# Macro_Keyboard_32u4_RC_SK6812_LED_Ver2_1.net
KiCad netlist of a schematic drawn in EAGLE
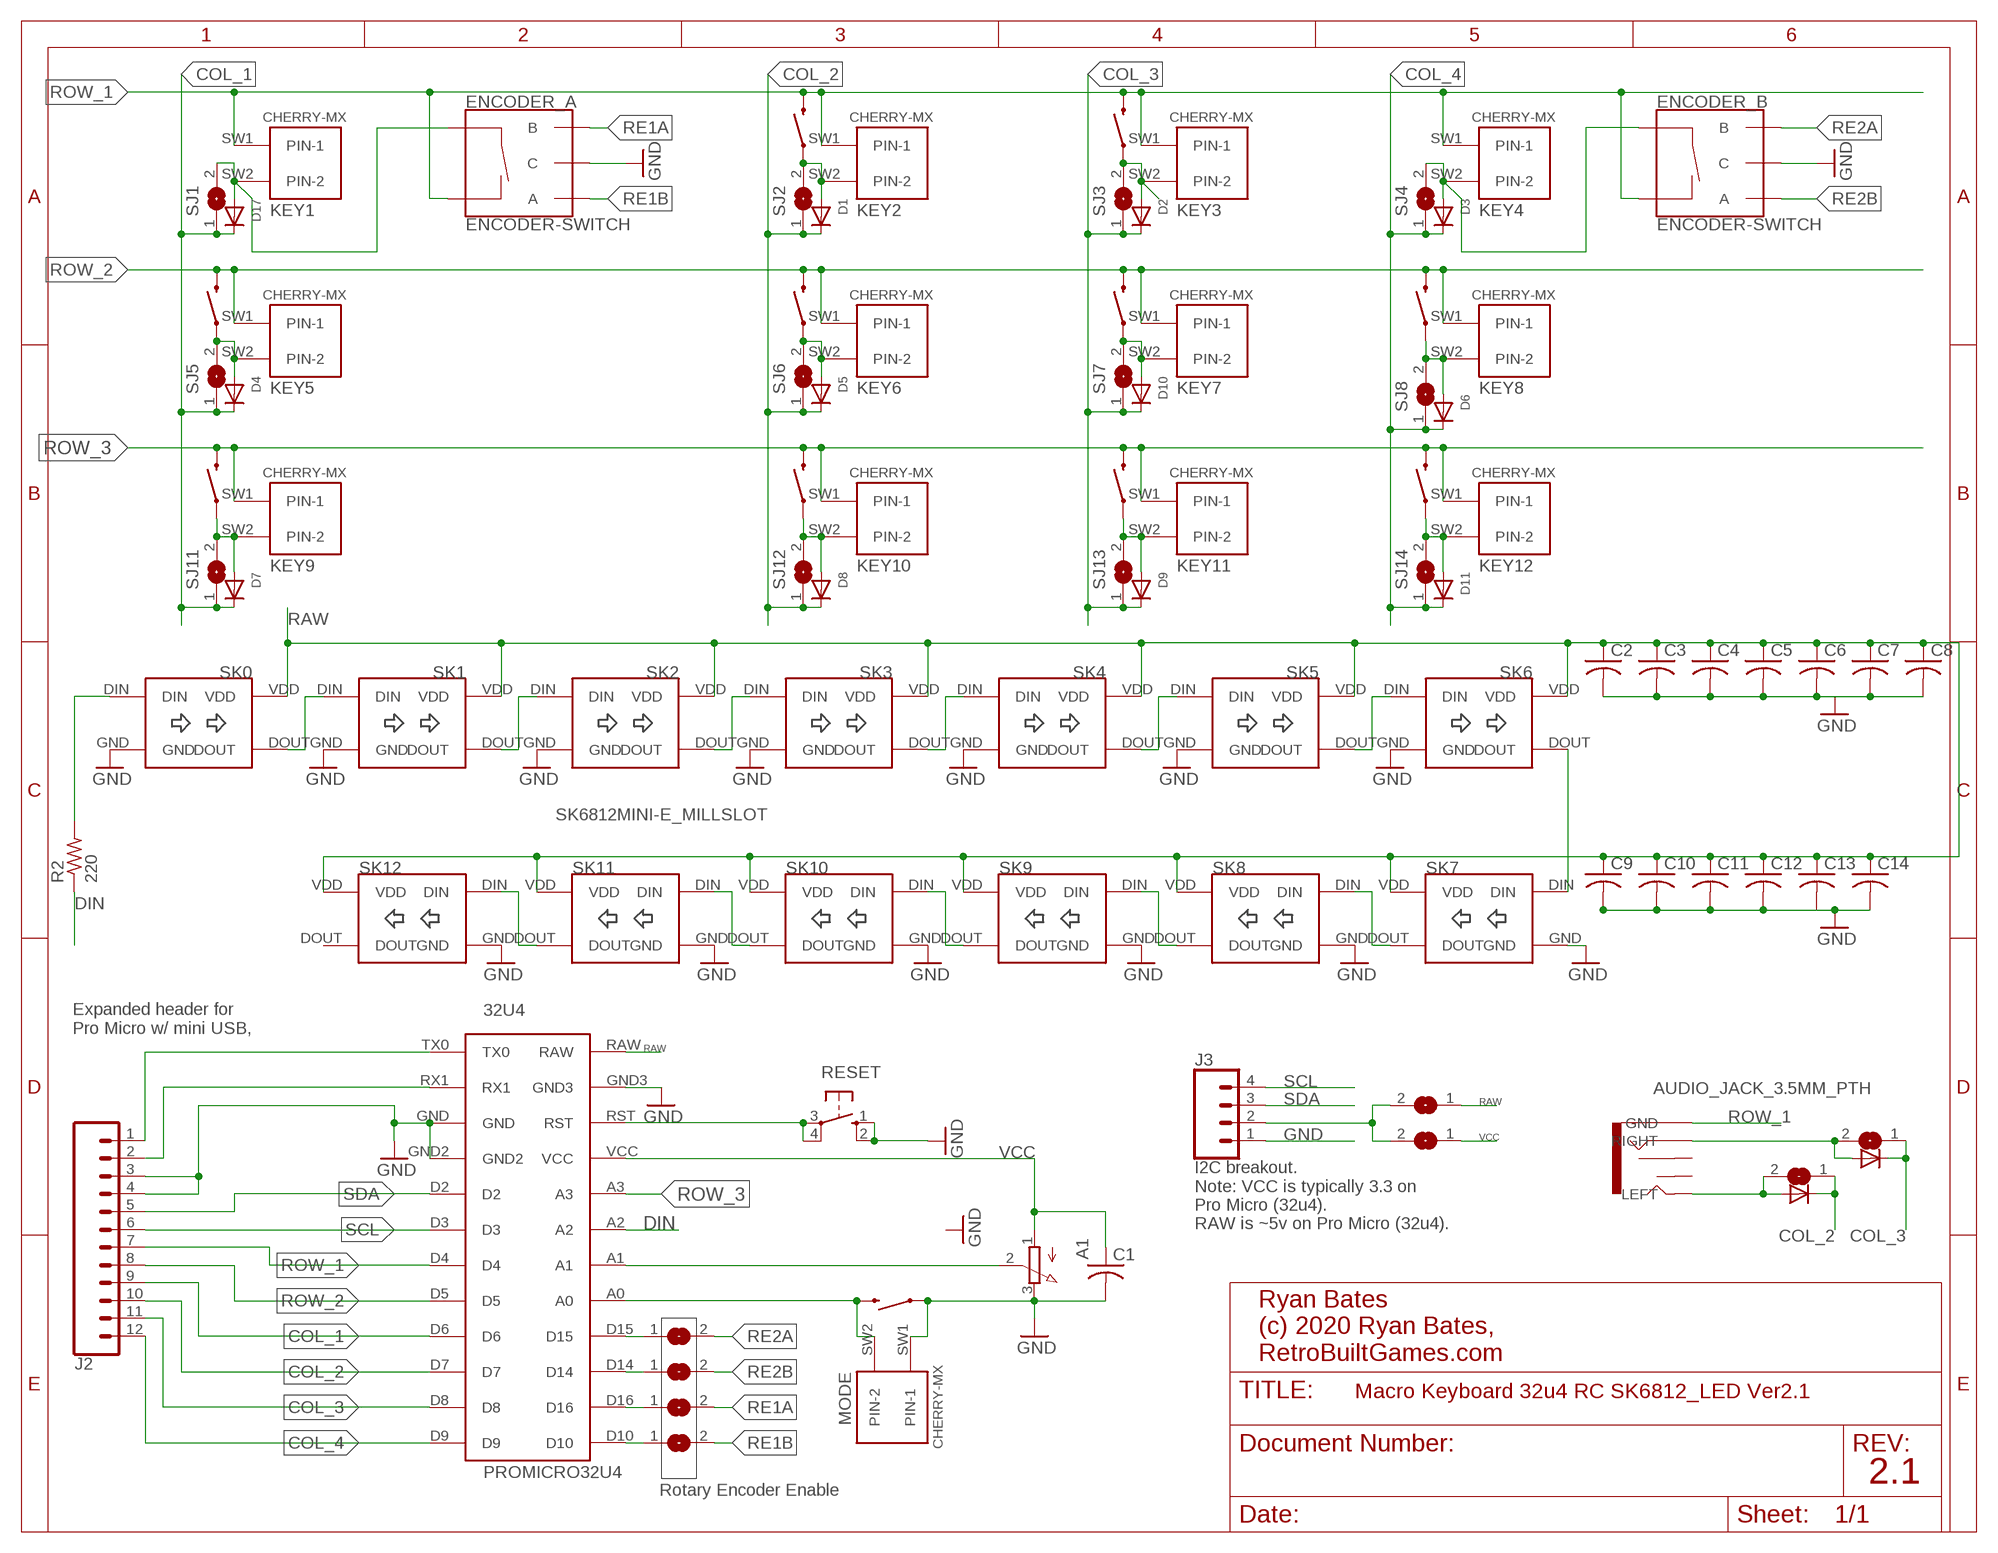
[diagram p0: schematic, sheet 1]

(export (version "E")
  (design (tool "Eeschema 10.0.6"))
  (components
    (comp (ref "32U4")
      (value "PROMICRO32U4")
      (footprint "eagle-import:PROMICRO32U4")
      (libsource (lib "eagle-import") (part "PROMICRO32U4"))
    )
    (comp (ref "A1")
      (value "3RP/1610N")
      (footprint "eagle-import:3RP_1610N")
      (libsource (lib "eagle-import") (part "3RP/1610N"))
    )
    (comp (ref "C1")
      (value "C-USC1206")
      (footprint "eagle-import:C1206")
      (libsource (lib "eagle-import") (part "C-USC1206"))
    )
    (comp (ref "C2")
      (value "C-USC0805K")
      (footprint "eagle-import:C0805K")
      (libsource (lib "eagle-import") (part "C-USC0805K"))
    )
    (comp (ref "C3")
      (value "C-USC0805K")
      (footprint "eagle-import:C0805K")
      (libsource (lib "eagle-import") (part "C-USC0805K"))
    )
    (comp (ref "C4")
      (value "C-USC0805K")
      (footprint "eagle-import:C0805K")
      (libsource (lib "eagle-import") (part "C-USC0805K"))
    )
    (comp (ref "C5")
      (value "C-USC0805K")
      (footprint "eagle-import:C0805K")
      (libsource (lib "eagle-import") (part "C-USC0805K"))
    )
    (comp (ref "C6")
      (value "C-USC0805K")
      (footprint "eagle-import:C0805K")
      (libsource (lib "eagle-import") (part "C-USC0805K"))
    )
    (comp (ref "C7")
      (value "C-USC0805K")
      (footprint "eagle-import:C0805K")
      (libsource (lib "eagle-import") (part "C-USC0805K"))
    )
    (comp (ref "C8")
      (value "C-USC0805K")
      (footprint "eagle-import:C0805K")
      (libsource (lib "eagle-import") (part "C-USC0805K"))
    )
    (comp (ref "C9")
      (value "C-USC0805K")
      (footprint "eagle-import:C0805K")
      (libsource (lib "eagle-import") (part "C-USC0805K"))
    )
    (comp (ref "C10")
      (value "C-USC0805K")
      (footprint "eagle-import:C0805K")
      (libsource (lib "eagle-import") (part "C-USC0805K"))
    )
    (comp (ref "C11")
      (value "C-USC0805K")
      (footprint "eagle-import:C0805K")
      (libsource (lib "eagle-import") (part "C-USC0805K"))
    )
    (comp (ref "C12")
      (value "C-USC0805K")
      (footprint "eagle-import:C0805K")
      (libsource (lib "eagle-import") (part "C-USC0805K"))
    )
    (comp (ref "C13")
      (value "C-USC0805K")
      (footprint "eagle-import:C0805K")
      (libsource (lib "eagle-import") (part "C-USC0805K"))
    )
    (comp (ref "C14")
      (value "C-USC0805K")
      (footprint "eagle-import:C0805K")
      (libsource (lib "eagle-import") (part "C-USC0805K"))
    )
    (comp (ref "D1")
      (value "DIODESOD-123")
      (footprint "eagle-import:SOD-123")
      (libsource (lib "eagle-import") (part "DIODESOD-123"))
    )
    (comp (ref "D2")
      (value "DIODESOD-123")
      (footprint "eagle-import:SOD-123")
      (libsource (lib "eagle-import") (part "DIODESOD-123"))
    )
    (comp (ref "D3")
      (value "DIODESOD-123")
      (footprint "eagle-import:SOD-123")
      (libsource (lib "eagle-import") (part "DIODESOD-123"))
    )
    (comp (ref "D4")
      (value "DIODESOD-123")
      (footprint "eagle-import:SOD-123")
      (libsource (lib "eagle-import") (part "DIODESOD-123"))
    )
    (comp (ref "D5")
      (value "DIODESOD-123")
      (footprint "eagle-import:SOD-123")
      (libsource (lib "eagle-import") (part "DIODESOD-123"))
    )
    (comp (ref "D6")
      (value "DIODESOD-123")
      (footprint "eagle-import:SOD-123")
      (libsource (lib "eagle-import") (part "DIODESOD-123"))
    )
    (comp (ref "D7")
      (value "DIODESOD-123")
      (footprint "eagle-import:SOD-123")
      (libsource (lib "eagle-import") (part "DIODESOD-123"))
    )
    (comp (ref "D8")
      (value "DIODESOD-123")
      (footprint "eagle-import:SOD-123")
      (libsource (lib "eagle-import") (part "DIODESOD-123"))
    )
    (comp (ref "D9")
      (value "DIODESOD-123")
      (footprint "eagle-import:SOD-123")
      (libsource (lib "eagle-import") (part "DIODESOD-123"))
    )
    (comp (ref "D10")
      (value "DIODESOD-123")
      (footprint "eagle-import:SOD-123")
      (libsource (lib "eagle-import") (part "DIODESOD-123"))
    )
    (comp (ref "D11")
      (value "DIODESOD-123")
      (footprint "eagle-import:SOD-123")
      (libsource (lib "eagle-import") (part "DIODESOD-123"))
    )
    (comp (ref "D15")
      (value "DIODESOD-123")
      (footprint "eagle-import:SOD-123")
      (libsource (lib "eagle-import") (part "DIODESOD-123"))
    )
    (comp (ref "D16")
      (value "DIODESOD-123")
      (footprint "eagle-import:SOD-123")
      (libsource (lib "eagle-import") (part "DIODESOD-123"))
    )
    (comp (ref "D17")
      (value "DIODESOD-123")
      (footprint "eagle-import:SOD-123")
      (libsource (lib "eagle-import") (part "DIODESOD-123"))
    )
    (comp (ref "ENCODER_A")
      (value "ENCODER-SWITCH")
      (footprint "eagle-import:ROTARY_ENC_PLAIN")
      (libsource (lib "eagle-import") (part "ENCODER-SWITCH"))
    )
    (comp (ref "ENCODER_B")
      (value "ENCODER-SWITCH")
      (footprint "eagle-import:ROTARY_ENC_PLAIN")
      (libsource (lib "eagle-import") (part "ENCODER-SWITCH"))
    )
    (comp (ref "J1")
      (value "AUDIO_JACK_3.5MM_PTH")
      (footprint "eagle-import:AUDIO-JACK")
      (libsource (lib "eagle-import") (part "AUDIO_JACK_3.5MM_PTH"))
    )
    (comp (ref "J2")
      (value "CONN_12NO_SILK")
      (footprint "eagle-import:1X12_NO_SILK")
      (libsource (lib "eagle-import") (part "CONN_12NO_SILK"))
    )
    (comp (ref "J3")
      (value "CONN_041X04_NO_SILK")
      (footprint "eagle-import:1X04_NO_SILK")
      (libsource (lib "eagle-import") (part "CONN_041X04_NO_SILK"))
    )
    (comp (ref "KEY1")
      (value "CHERRY-MX")
      (footprint "eagle-import:CHERRY-MX")
      (libsource (lib "eagle-import") (part "CHERRY-MX"))
    )
    (comp (ref "KEY2")
      (value "CHERRY-MX")
      (footprint "eagle-import:CHERRY-MX")
      (libsource (lib "eagle-import") (part "CHERRY-MX"))
    )
    (comp (ref "KEY3")
      (value "CHERRY-MX")
      (footprint "eagle-import:CHERRY-MX")
      (libsource (lib "eagle-import") (part "CHERRY-MX"))
    )
    (comp (ref "KEY4")
      (value "CHERRY-MX")
      (footprint "eagle-import:CHERRY-MX")
      (libsource (lib "eagle-import") (part "CHERRY-MX"))
    )
    (comp (ref "KEY5")
      (value "CHERRY-MX")
      (footprint "eagle-import:CHERRY-MX")
      (libsource (lib "eagle-import") (part "CHERRY-MX"))
    )
    (comp (ref "KEY6")
      (value "CHERRY-MX")
      (footprint "eagle-import:CHERRY-MX")
      (libsource (lib "eagle-import") (part "CHERRY-MX"))
    )
    (comp (ref "KEY7")
      (value "CHERRY-MX")
      (footprint "eagle-import:CHERRY-MX")
      (libsource (lib "eagle-import") (part "CHERRY-MX"))
    )
    (comp (ref "KEY8")
      (value "CHERRY-MX")
      (footprint "eagle-import:CHERRY-MX")
      (libsource (lib "eagle-import") (part "CHERRY-MX"))
    )
    (comp (ref "KEY9")
      (value "CHERRY-MX")
      (footprint "eagle-import:CHERRY-MX")
      (libsource (lib "eagle-import") (part "CHERRY-MX"))
    )
    (comp (ref "KEY10")
      (value "CHERRY-MX")
      (footprint "eagle-import:CHERRY-MX")
      (libsource (lib "eagle-import") (part "CHERRY-MX"))
    )
    (comp (ref "KEY11")
      (value "CHERRY-MX")
      (footprint "eagle-import:CHERRY-MX")
      (libsource (lib "eagle-import") (part "CHERRY-MX"))
    )
    (comp (ref "KEY12")
      (value "CHERRY-MX")
      (footprint "eagle-import:CHERRY-MX")
      (libsource (lib "eagle-import") (part "CHERRY-MX"))
    )
    (comp (ref "MODE")
      (value "CHERRY-MX")
      (footprint "eagle-import:CHERRY-MX")
      (libsource (lib "eagle-import") (part "CHERRY-MX"))
    )
    (comp (ref "R2")
      (value "220")
      (footprint "eagle-import:M1206")
      (libsource (lib "eagle-import") (part "R-US_M1206"))
    )
    (comp (ref "RESET")
      (value "10-XX")
      (footprint "eagle-import:B3F-10XX")
      (fields (field (name "MPN") "B3F-1000"))
      (libsource (lib "eagle-import") (part "10-XX"))
    )
    (comp (ref "S1")
      (value "MOMENTARY-SWITCH-SPST-PTH-12MM")
      (footprint "eagle-import:TACTILE_SWITCH_PTH_12MM")
      (libsource (lib "eagle-import") (part "MOMENTARY-SWITCH-SPST-PTH-12MM"))
    )
    (comp (ref "S2")
      (value "MOMENTARY-SWITCH-SPST-PTH-12MM")
      (footprint "eagle-import:TACTILE_SWITCH_PTH_12MM")
      (libsource (lib "eagle-import") (part "MOMENTARY-SWITCH-SPST-PTH-12MM"))
    )
    (comp (ref "S3")
      (value "MOMENTARY-SWITCH-SPST-PTH-12MM")
      (footprint "eagle-import:TACTILE_SWITCH_PTH_12MM")
      (libsource (lib "eagle-import") (part "MOMENTARY-SWITCH-SPST-PTH-12MM"))
    )
    (comp (ref "S4")
      (value "MOMENTARY-SWITCH-SPST-PTH-12MM")
      (footprint "eagle-import:TACTILE_SWITCH_PTH_12MM")
      (libsource (lib "eagle-import") (part "MOMENTARY-SWITCH-SPST-PTH-12MM"))
    )
    (comp (ref "S5")
      (value "MOMENTARY-SWITCH-SPST-PTH-12MM")
      (footprint "eagle-import:TACTILE_SWITCH_PTH_12MM")
      (libsource (lib "eagle-import") (part "MOMENTARY-SWITCH-SPST-PTH-12MM"))
    )
    (comp (ref "S6")
      (value "MOMENTARY-SWITCH-SPST-PTH-12MM")
      (footprint "eagle-import:TACTILE_SWITCH_PTH_12MM")
      (libsource (lib "eagle-import") (part "MOMENTARY-SWITCH-SPST-PTH-12MM"))
    )
    (comp (ref "S7")
      (value "MOMENTARY-SWITCH-SPST-PTH-12MM")
      (footprint "eagle-import:TACTILE_SWITCH_PTH_12MM")
      (libsource (lib "eagle-import") (part "MOMENTARY-SWITCH-SPST-PTH-12MM"))
    )
    (comp (ref "S8")
      (value "MOMENTARY-SWITCH-SPST-PTH-12MM")
      (footprint "eagle-import:TACTILE_SWITCH_PTH_12MM")
      (libsource (lib "eagle-import") (part "MOMENTARY-SWITCH-SPST-PTH-12MM"))
    )
    (comp (ref "S9")
      (value "MOMENTARY-SWITCH-SPST-PTH-12MM")
      (footprint "eagle-import:TACTILE_SWITCH_PTH_12MM")
      (libsource (lib "eagle-import") (part "MOMENTARY-SWITCH-SPST-PTH-12MM"))
    )
    (comp (ref "S10")
      (value "MOMENTARY-SWITCH-SPST-PTH-12MM")
      (footprint "eagle-import:TACTILE_SWITCH_PTH_12MM")
      (libsource (lib "eagle-import") (part "MOMENTARY-SWITCH-SPST-PTH-12MM"))
    )
    (comp (ref "S11")
      (value "MOMENTARY-SWITCH-SPST-PTH-12MM")
      (footprint "eagle-import:TACTILE_SWITCH_PTH_12MM")
      (libsource (lib "eagle-import") (part "MOMENTARY-SWITCH-SPST-PTH-12MM"))
    )
    (comp (ref "SJ1") (value "SJ") (footprint "eagle-import:SJ") (libsource (lib "eagle-import") (part "SJ")))
    (comp (ref "SJ2") (value "SJ") (footprint "eagle-import:SJ") (libsource (lib "eagle-import") (part "SJ")))
    (comp (ref "SJ3") (value "SJ") (footprint "eagle-import:SJ") (libsource (lib "eagle-import") (part "SJ")))
    (comp (ref "SJ4") (value "SJ") (footprint "eagle-import:SJ") (libsource (lib "eagle-import") (part "SJ")))
    (comp (ref "SJ5") (value "SJ") (footprint "eagle-import:SJ") (libsource (lib "eagle-import") (part "SJ")))
    (comp (ref "SJ6") (value "SJ") (footprint "eagle-import:SJ") (libsource (lib "eagle-import") (part "SJ")))
    (comp (ref "SJ7") (value "SJ") (footprint "eagle-import:SJ") (libsource (lib "eagle-import") (part "SJ")))
    (comp (ref "SJ8") (value "SJ") (footprint "eagle-import:SJ") (libsource (lib "eagle-import") (part "SJ")))
    (comp (ref "SJ9") (value "SJ") (footprint "eagle-import:SJ") (libsource (lib "eagle-import") (part "SJ")))
    (comp (ref "SJ10")
      (value "SJ")
      (footprint "eagle-import:SJ")
      (libsource (lib "eagle-import") (part "SJ"))
    )
    (comp (ref "SJ11")
      (value "SJ")
      (footprint "eagle-import:SJ")
      (libsource (lib "eagle-import") (part "SJ"))
    )
    (comp (ref "SJ12")
      (value "SJ")
      (footprint "eagle-import:SJ")
      (libsource (lib "eagle-import") (part "SJ"))
    )
    (comp (ref "SJ13")
      (value "SJ")
      (footprint "eagle-import:SJ")
      (libsource (lib "eagle-import") (part "SJ"))
    )
    (comp (ref "SJ14")
      (value "SJ")
      (footprint "eagle-import:SJ")
      (libsource (lib "eagle-import") (part "SJ"))
    )
    (comp (ref "SJ16")
      (value "SJ")
      (footprint "eagle-import:SJ")
      (libsource (lib "eagle-import") (part "SJ"))
    )
    (comp (ref "SJ17")
      (value "SJ")
      (footprint "eagle-import:SJ")
      (libsource (lib "eagle-import") (part "SJ"))
    )
    (comp (ref "SJ18")
      (value "SJ")
      (footprint "eagle-import:SJ")
      (libsource (lib "eagle-import") (part "SJ"))
    )
    (comp (ref "SJ19")
      (value "SJ")
      (footprint "eagle-import:SJ")
      (libsource (lib "eagle-import") (part "SJ"))
    )
    (comp (ref "SJ20")
      (value "SJ")
      (footprint "eagle-import:SJ")
      (libsource (lib "eagle-import") (part "SJ"))
    )
    (comp (ref "SJ21")
      (value "SJ")
      (footprint "eagle-import:SJ")
      (libsource (lib "eagle-import") (part "SJ"))
    )
    (comp (ref "SK0")
      (value "SK6812MINI-E_MILLSLOT")
      (footprint "eagle-import:SK6812MINI-E_MILLSLOT")
      (libsource (lib "eagle-import") (part "SK6812MINI-E_MILLSLOT"))
    )
    (comp (ref "SK1")
      (value "SK6812MINI-E_MILLSLOT")
      (footprint "eagle-import:SK6812MINI-E_MILLSLOT")
      (libsource (lib "eagle-import") (part "SK6812MINI-E_MILLSLOT"))
    )
    (comp (ref "SK2")
      (value "SK6812MINI-E_MILLSLOT")
      (footprint "eagle-import:SK6812MINI-E_MILLSLOT")
      (libsource (lib "eagle-import") (part "SK6812MINI-E_MILLSLOT"))
    )
    (comp (ref "SK3")
      (value "SK6812MINI-E_MILLSLOT")
      (footprint "eagle-import:SK6812MINI-E_MILLSLOT")
      (libsource (lib "eagle-import") (part "SK6812MINI-E_MILLSLOT"))
    )
    (comp (ref "SK4")
      (value "SK6812MINI-E_MILLSLOT")
      (footprint "eagle-import:SK6812MINI-E_MILLSLOT")
      (libsource (lib "eagle-import") (part "SK6812MINI-E_MILLSLOT"))
    )
    (comp (ref "SK5")
      (value "SK6812MINI-E_MILLSLOT")
      (footprint "eagle-import:SK6812MINI-E_MILLSLOT")
      (libsource (lib "eagle-import") (part "SK6812MINI-E_MILLSLOT"))
    )
    (comp (ref "SK6")
      (value "SK6812MINI-E_MILLSLOT")
      (footprint "eagle-import:SK6812MINI-E_MILLSLOT")
      (libsource (lib "eagle-import") (part "SK6812MINI-E_MILLSLOT"))
    )
    (comp (ref "SK7")
      (value "SK6812MINI-E_MILLSLOT")
      (footprint "eagle-import:SK6812MINI-E_MILLSLOT")
      (libsource (lib "eagle-import") (part "SK6812MINI-E_MILLSLOT"))
    )
    (comp (ref "SK8")
      (value "SK6812MINI-E_MILLSLOT")
      (footprint "eagle-import:SK6812MINI-E_MILLSLOT")
      (libsource (lib "eagle-import") (part "SK6812MINI-E_MILLSLOT"))
    )
    (comp (ref "SK9")
      (value "SK6812MINI-E_MILLSLOT")
      (footprint "eagle-import:SK6812MINI-E_MILLSLOT")
      (libsource (lib "eagle-import") (part "SK6812MINI-E_MILLSLOT"))
    )
    (comp (ref "SK10")
      (value "SK6812MINI-E_MILLSLOT")
      (footprint "eagle-import:SK6812MINI-E_MILLSLOT")
      (libsource (lib "eagle-import") (part "SK6812MINI-E_MILLSLOT"))
    )
    (comp (ref "SK11")
      (value "SK6812MINI-E_MILLSLOT")
      (footprint "eagle-import:SK6812MINI-E_MILLSLOT")
      (libsource (lib "eagle-import") (part "SK6812MINI-E_MILLSLOT"))
    )
    (comp (ref "SK12")
      (value "SK6812MINI-E_MILLSLOT")
      (footprint "eagle-import:SK6812MINI-E_MILLSLOT")
      (libsource (lib "eagle-import") (part "SK6812MINI-E_MILLSLOT"))
    )
  )
  (nets
    (net (code "1") (name "/DIN") (class "Default")
      (node (ref "32U4") (pin "A2") (pinfunction "A2_A2") (pintype "bidirectional"))
      (node (ref "R2") (pin "1") (pinfunction "1_1") (pintype "passive"))
    )
    (net (code "2") (name "/RAW") (class "Default")
      (node (ref "32U4") (pin "RAW") (pinfunction "RAW_RAW") (pintype "bidirectional"))
      (node (ref "C10") (pin "1") (pinfunction "1_1") (pintype "passive"))
      (node (ref "C11") (pin "1") (pinfunction "1_1") (pintype "passive"))
      (node (ref "C12") (pin "1") (pinfunction "1_1") (pintype "passive"))
      (node (ref "C13") (pin "1") (pinfunction "1_1") (pintype "passive"))
      (node (ref "C14") (pin "1") (pinfunction "1_1") (pintype "passive"))
      (node (ref "C2") (pin "1") (pinfunction "1_1") (pintype "passive"))
      (node (ref "C3") (pin "1") (pinfunction "1_1") (pintype "passive"))
      (node (ref "C4") (pin "1") (pinfunction "1_1") (pintype "passive"))
      (node (ref "C5") (pin "1") (pinfunction "1_1") (pintype "passive"))
      (node (ref "C6") (pin "1") (pinfunction "1_1") (pintype "passive"))
      (node (ref "C7") (pin "1") (pinfunction "1_1") (pintype "passive"))
      (node (ref "C8") (pin "1") (pinfunction "1_1") (pintype "passive"))
      (node (ref "C9") (pin "1") (pinfunction "1_1") (pintype "passive"))
      (node (ref "SJ9") (pin "1") (pinfunction "1_1") (pintype "passive"))
      (node (ref "SK0") (pin "VDD") (pinfunction "VDD_VDD") (pintype "bidirectional"))
      (node (ref "SK1") (pin "VDD") (pinfunction "VDD_VDD") (pintype "bidirectional"))
      (node (ref "SK10") (pin "VDD") (pinfunction "VDD_VDD") (pintype "bidirectional"))
      (node (ref "SK11") (pin "VDD") (pinfunction "VDD_VDD") (pintype "bidirectional"))
      (node (ref "SK12") (pin "VDD") (pinfunction "VDD_VDD") (pintype "bidirectional"))
      (node (ref "SK2") (pin "VDD") (pinfunction "VDD_VDD") (pintype "bidirectional"))
      (node (ref "SK3") (pin "VDD") (pinfunction "VDD_VDD") (pintype "bidirectional"))
      (node (ref "SK4") (pin "VDD") (pinfunction "VDD_VDD") (pintype "bidirectional"))
      (node (ref "SK5") (pin "VDD") (pinfunction "VDD_VDD") (pintype "bidirectional"))
      (node (ref "SK6") (pin "VDD") (pinfunction "VDD_VDD") (pintype "bidirectional"))
      (node (ref "SK7") (pin "VDD") (pinfunction "VDD_VDD") (pintype "bidirectional"))
      (node (ref "SK8") (pin "VDD") (pinfunction "VDD_VDD") (pintype "bidirectional"))
      (node (ref "SK9") (pin "VDD") (pinfunction "VDD_VDD") (pintype "bidirectional"))
    )
    (net (code "3") (name "/VCC") (class "Default")
      (node (ref "32U4") (pin "VCC") (pinfunction "VCC_VCC") (pintype "bidirectional"))
      (node (ref "A1") (pin "1") (pinfunction "A_1") (pintype "passive"))
      (node (ref "C1") (pin "1") (pinfunction "1_1") (pintype "passive"))
      (node (ref "SJ10") (pin "1") (pinfunction "1_1") (pintype "passive"))
    )
    (net (code "4") (name "COL_1") (class "Default")
      (node (ref "32U4") (pin "D6") (pinfunction "D6_D6") (pintype "bidirectional"))
      (node (ref "D17") (pin "C") (pinfunction "C_C") (pintype "passive"))
      (node (ref "D4") (pin "C") (pinfunction "C_C") (pintype "passive"))
      (node (ref "D7") (pin "C") (pinfunction "C_C") (pintype "passive"))
      (node (ref "J2") (pin "9") (pinfunction "9_9") (pintype "passive"))
      (node (ref "SJ1") (pin "1") (pinfunction "1_1") (pintype "passive"))
      (node (ref "SJ11") (pin "1") (pinfunction "1_1") (pintype "passive"))
      (node (ref "SJ5") (pin "1") (pinfunction "1_1") (pintype "passive"))
    )
    (net (code "5") (name "COL_2") (class "Default")
      (node (ref "32U4") (pin "D7") (pinfunction "D7_D7") (pintype "bidirectional"))
      (node (ref "D1") (pin "C") (pinfunction "C_C") (pintype "passive"))
      (node (ref "D15") (pin "C") (pinfunction "C_C") (pintype "passive"))
      (node (ref "D5") (pin "C") (pinfunction "C_C") (pintype "passive"))
      (node (ref "D8") (pin "C") (pinfunction "C_C") (pintype "passive"))
      (node (ref "J2") (pin "10") (pinfunction "10_10") (pintype "passive"))
      (node (ref "SJ12") (pin "1") (pinfunction "1_1") (pintype "passive"))
      (node (ref "SJ16") (pin "1") (pinfunction "1_1") (pintype "passive"))
      (node (ref "SJ2") (pin "1") (pinfunction "1_1") (pintype "passive"))
      (node (ref "SJ6") (pin "1") (pinfunction "1_1") (pintype "passive"))
    )
    (net (code "6") (name "COL_3") (class "Default")
      (node (ref "32U4") (pin "D8") (pinfunction "D8_D8") (pintype "bidirectional"))
      (node (ref "D10") (pin "C") (pinfunction "C_C") (pintype "passive"))
      (node (ref "D16") (pin "C") (pinfunction "C_C") (pintype "passive"))
      (node (ref "D2") (pin "C") (pinfunction "C_C") (pintype "passive"))
      (node (ref "D9") (pin "C") (pinfunction "C_C") (pintype "passive"))
      (node (ref "J2") (pin "11") (pinfunction "11_11") (pintype "passive"))
      (node (ref "SJ13") (pin "1") (pinfunction "1_1") (pintype "passive"))
      (node (ref "SJ17") (pin "1") (pinfunction "1_1") (pintype "passive"))
      (node (ref "SJ3") (pin "1") (pinfunction "1_1") (pintype "passive"))
      (node (ref "SJ7") (pin "1") (pinfunction "1_1") (pintype "passive"))
    )
    (net (code "7") (name "COL_4") (class "Default")
      (node (ref "32U4") (pin "D9") (pinfunction "D9_D9") (pintype "bidirectional"))
      (node (ref "D11") (pin "C") (pinfunction "C_C") (pintype "passive"))
      (node (ref "D3") (pin "C") (pinfunction "C_C") (pintype "passive"))
      (node (ref "D6") (pin "C") (pinfunction "C_C") (pintype "passive"))
      (node (ref "J2") (pin "12") (pinfunction "12_12") (pintype "passive"))
      (node (ref "SJ14") (pin "1") (pinfunction "1_1") (pintype "passive"))
      (node (ref "SJ4") (pin "1") (pinfunction "1_1") (pintype "passive"))
      (node (ref "SJ8") (pin "1") (pinfunction "1_1") (pintype "passive"))
    )
    (net (code "8") (name "GND") (class "Default")
      (node (ref "32U4") (pin "GND") (pinfunction "GND_GND") (pintype "bidirectional"))
      (node (ref "32U4") (pin "GND2") (pinfunction "GND2_GND2") (pintype "bidirectional"))
      (node (ref "32U4") (pin "GND3") (pinfunction "GND3_GND3") (pintype "bidirectional"))
      (node (ref "A1") (pin "3") (pinfunction "E_3") (pintype "passive"))
      (node (ref "C1") (pin "2") (pinfunction "2_2") (pintype "passive"))
      (node (ref "C10") (pin "2") (pinfunction "2_2") (pintype "passive"))
      (node (ref "C11") (pin "2") (pinfunction "2_2") (pintype "passive"))
      (node (ref "C12") (pin "2") (pinfunction "2_2") (pintype "passive"))
      (node (ref "C13") (pin "2") (pinfunction "2_2") (pintype "passive"))
      (node (ref "C14") (pin "2") (pinfunction "2_2") (pintype "passive"))
      (node (ref "C2") (pin "2") (pinfunction "2_2") (pintype "passive"))
      (node (ref "C3") (pin "2") (pinfunction "2_2") (pintype "passive"))
      (node (ref "C4") (pin "2") (pinfunction "2_2") (pintype "passive"))
      (node (ref "C5") (pin "2") (pinfunction "2_2") (pintype "passive"))
      (node (ref "C6") (pin "2") (pinfunction "2_2") (pintype "passive"))
      (node (ref "C7") (pin "2") (pinfunction "2_2") (pintype "passive"))
      (node (ref "C8") (pin "2") (pinfunction "2_2") (pintype "passive"))
      (node (ref "C9") (pin "2") (pinfunction "2_2") (pintype "passive"))
      (node (ref "ENCODER_A") (pin "C") (pinfunction "C_C") (pintype "bidirectional"))
      (node (ref "ENCODER_B") (pin "C") (pinfunction "C_C") (pintype "bidirectional"))
      (node (ref "J2") (pin "3") (pinfunction "3_3") (pintype "passive"))
      (node (ref "J2") (pin "4") (pinfunction "4_4") (pintype "passive"))
      (node (ref "J3") (pin "1") (pinfunction "1_1") (pintype "passive"))
      (node (ref "MODE") (pin "SW1") (pinfunction "PIN-1_SW1") (pintype "bidirectional"))
      (node (ref "RESET") (pin "1") (pinfunction "S_1") (pintype "passive"))
      (node (ref "RESET") (pin "2") (pinfunction "S1_2") (pintype "passive"))
      (node (ref "S11") (pin "1") (pinfunction "1_1") (pintype "passive"))
      (node (ref "SK0") (pin "GND") (pinfunction "GND_GND") (pintype "bidirectional"))
      (node (ref "SK1") (pin "GND") (pinfunction "GND_GND") (pintype "bidirectional"))
      (node (ref "SK10") (pin "GND") (pinfunction "GND_GND") (pintype "bidirectional"))
      (node (ref "SK11") (pin "GND") (pinfunction "GND_GND") (pintype "bidirectional"))
      (node (ref "SK12") (pin "GND") (pinfunction "GND_GND") (pintype "bidirectional"))
      (node (ref "SK2") (pin "GND") (pinfunction "GND_GND") (pintype "bidirectional"))
      (node (ref "SK3") (pin "GND") (pinfunction "GND_GND") (pintype "bidirectional"))
      (node (ref "SK4") (pin "GND") (pinfunction "GND_GND") (pintype "bidirectional"))
      (node (ref "SK5") (pin "GND") (pinfunction "GND_GND") (pintype "bidirectional"))
      (node (ref "SK6") (pin "GND") (pinfunction "GND_GND") (pintype "bidirectional"))
      (node (ref "SK7") (pin "GND") (pinfunction "GND_GND") (pintype "bidirectional"))
      (node (ref "SK8") (pin "GND") (pinfunction "GND_GND") (pintype "bidirectional"))
      (node (ref "SK9") (pin "GND") (pinfunction "GND_GND") (pintype "bidirectional"))
    )
    (net (code "9") (name "Net-(32U4-PadD10)") (class "Default")
      (node (ref "32U4") (pin "D10") (pinfunction "D10_D10") (pintype "bidirectional"))
      (node (ref "SJ21") (pin "1") (pinfunction "1_1") (pintype "passive"))
    )
    (net (code "10") (name "Net-(32U4-PadD14)") (class "Default")
      (node (ref "32U4") (pin "D14") (pinfunction "D14_D14") (pintype "bidirectional"))
      (node (ref "SJ19") (pin "1") (pinfunction "1_1") (pintype "passive"))
    )
    (net (code "11") (name "Net-(32U4-PadD15)") (class "Default")
      (node (ref "32U4") (pin "D15") (pinfunction "D15_D15") (pintype "bidirectional"))
      (node (ref "SJ18") (pin "1") (pinfunction "1_1") (pintype "passive"))
    )
    (net (code "12") (name "Net-(32U4-PadD16)") (class "Default")
      (node (ref "32U4") (pin "D16") (pinfunction "D16_D16") (pintype "bidirectional"))
      (node (ref "SJ20") (pin "1") (pinfunction "1_1") (pintype "passive"))
    )
    (net (code "13") (name "Net-(32U4-PadRX1)") (class "Default")
      (node (ref "32U4") (pin "RX1") (pinfunction "RX1_RX1") (pintype "bidirectional"))
      (node (ref "J2") (pin "2") (pinfunction "2_2") (pintype "passive"))
    )
    (net (code "14") (name "Net-(32U4-PadTX0)") (class "Default")
      (node (ref "32U4") (pin "TX0") (pinfunction "TX0_TX0") (pintype "bidirectional"))
      (node (ref "J2") (pin "1") (pinfunction "1_1") (pintype "passive"))
    )
    (net (code "15") (name "Net-(A1-S)") (class "Default")
      (node (ref "32U4") (pin "A1") (pinfunction "A1_A1") (pintype "bidirectional"))
      (node (ref "A1") (pin "2") (pinfunction "S_2") (pintype "passive"))
    )
    (net (code "16") (name "Net-(D15-PadA)") (class "Default")
      (node (ref "D15") (pin "A") (pinfunction "A_A") (pintype "passive"))
      (node (ref "J1") (pin "LEFT") (pinfunction "LEFT_LEFT") (pintype "bidirectional"))
      (node (ref "SJ16") (pin "2") (pinfunction "2_2") (pintype "passive"))
    )
    (net (code "17") (name "Net-(D16-PadA)") (class "Default")
      (node (ref "D16") (pin "A") (pinfunction "A_A") (pintype "passive"))
      (node (ref "J1") (pin "RIGHT") (pinfunction "RIGHT_RIGHT") (pintype "bidirectional"))
      (node (ref "SJ17") (pin "2") (pinfunction "2_2") (pintype "passive"))
    )
    (net (code "18") (name "Net-(J3-Pad2)") (class "Default")
      (node (ref "J3") (pin "2") (pinfunction "2_2") (pintype "passive"))
      (node (ref "SJ10") (pin "2") (pinfunction "2_2") (pintype "passive"))
      (node (ref "SJ9") (pin "2") (pinfunction "2_2") (pintype "passive"))
    )
    (net (code "19") (name "Net-(KEY1-PIN-2)") (class "Default")
      (node (ref "D17") (pin "A") (pinfunction "A_A") (pintype "passive"))
      (node (ref "ENCODER_A") (pin "SW+") (pinfunction "SW+_SW+") (pintype "bidirectional"))
      (node (ref "KEY1") (pin "SW2") (pinfunction "PIN-2_SW2") (pintype "bidirectional"))
      (node (ref "SJ1") (pin "2") (pinfunction "2_2") (pintype "passive"))
    )
    (net (code "20") (name "Net-(KEY2-PIN-2)") (class "Default")
      (node (ref "D1") (pin "A") (pinfunction "A_A") (pintype "passive"))
      (node (ref "KEY2") (pin "SW2") (pinfunction "PIN-2_SW2") (pintype "bidirectional"))
      (node (ref "S4") (pin "1") (pinfunction "1_1") (pintype "passive"))
      (node (ref "SJ2") (pin "2") (pinfunction "2_2") (pintype "passive"))
    )
    (net (code "21") (name "Net-(KEY3-PIN-2)") (class "Default")
      (node (ref "D2") (pin "A") (pinfunction "A_A") (pintype "passive"))
      (node (ref "KEY3") (pin "SW2") (pinfunction "PIN-2_SW2") (pintype "bidirectional"))
      (node (ref "S3") (pin "1") (pinfunction "1_1") (pintype "passive"))
      (node (ref "SJ3") (pin "2") (pinfunction "2_2") (pintype "passive"))
    )
    (net (code "22") (name "Net-(KEY4-PIN-2)") (class "Default")
      (node (ref "D3") (pin "A") (pinfunction "A_A") (pintype "passive"))
      (node (ref "ENCODER_B") (pin "SW+") (pinfunction "SW+_SW+") (pintype "bidirectional"))
      (node (ref "KEY4") (pin "SW2") (pinfunction "PIN-2_SW2") (pintype "bidirectional"))
      (node (ref "SJ4") (pin "2") (pinfunction "2_2") (pintype "passive"))
    )
    (net (code "23") (name "Net-(KEY5-PIN-2)") (class "Default")
      (node (ref "D4") (pin "A") (pinfunction "A_A") (pintype "passive"))
      (node (ref "KEY5") (pin "SW2") (pinfunction "PIN-2_SW2") (pintype "bidirectional"))
      (node (ref "S9") (pin "1") (pinfunction "1_1") (pintype "passive"))
      (node (ref "SJ5") (pin "2") (pinfunction "2_2") (pintype "passive"))
    )
    (net (code "24") (name "Net-(KEY6-PIN-2)") (class "Default")
      (node (ref "D5") (pin "A") (pinfunction "A_A") (pintype "passive"))
      (node (ref "KEY6") (pin "SW2") (pinfunction "PIN-2_SW2") (pintype "bidirectional"))
      (node (ref "S10") (pin "1") (pinfunction "1_1") (pintype "passive"))
      (node (ref "SJ6") (pin "2") (pinfunction "2_2") (pintype "passive"))
    )
    (net (code "25") (name "Net-(KEY7-PIN-2)") (class "Default")
      (node (ref "D10") (pin "A") (pinfunction "A_A") (pintype "passive"))
      (node (ref "KEY7") (pin "SW2") (pinfunction "PIN-2_SW2") (pintype "bidirectional"))
      (node (ref "S1") (pin "1") (pinfunction "1_1") (pintype "passive"))
      (node (ref "SJ7") (pin "2") (pinfunction "2_2") (pintype "passive"))
    )
    (net (code "26") (name "Net-(KEY8-PIN-2)") (class "Default")
      (node (ref "D6") (pin "A") (pinfunction "A_A") (pintype "passive"))
      (node (ref "KEY8") (pin "SW2") (pinfunction "PIN-2_SW2") (pintype "bidirectional"))
      (node (ref "S2") (pin "1") (pinfunction "1_1") (pintype "passive"))
      (node (ref "SJ8") (pin "2") (pinfunction "2_2") (pintype "passive"))
    )
    (net (code "27") (name "Net-(KEY9-PIN-2)") (class "Default")
      (node (ref "D7") (pin "A") (pinfunction "A_A") (pintype "passive"))
      (node (ref "KEY9") (pin "SW2") (pinfunction "PIN-2_SW2") (pintype "bidirectional"))
      (node (ref "S5") (pin "1") (pinfunction "1_1") (pintype "passive"))
      (node (ref "SJ11") (pin "2") (pinfunction "2_2") (pintype "passive"))
    )
    (net (code "28") (name "Net-(KEY10-PIN-2)") (class "Default")
      (node (ref "D8") (pin "A") (pinfunction "A_A") (pintype "passive"))
      (node (ref "KEY10") (pin "SW2") (pinfunction "PIN-2_SW2") (pintype "bidirectional"))
      (node (ref "S6") (pin "1") (pinfunction "1_1") (pintype "passive"))
      (node (ref "SJ12") (pin "2") (pinfunction "2_2") (pintype "passive"))
    )
    (net (code "29") (name "Net-(KEY11-PIN-2)") (class "Default")
      (node (ref "D9") (pin "A") (pinfunction "A_A") (pintype "passive"))
      (node (ref "KEY11") (pin "SW2") (pinfunction "PIN-2_SW2") (pintype "bidirectional"))
      (node (ref "S7") (pin "1") (pinfunction "1_1") (pintype "passive"))
      (node (ref "SJ13") (pin "2") (pinfunction "2_2") (pintype "passive"))
    )
    (net (code "30") (name "Net-(KEY12-PIN-2)") (class "Default")
      (node (ref "D11") (pin "A") (pinfunction "A_A") (pintype "passive"))
      (node (ref "KEY12") (pin "SW2") (pinfunction "PIN-2_SW2") (pintype "bidirectional"))
      (node (ref "S8") (pin "1") (pinfunction "1_1") (pintype "passive"))
      (node (ref "SJ14") (pin "2") (pinfunction "2_2") (pintype "passive"))
    )
    (net (code "31") (name "Net-(MODE-PIN-2)") (class "Default")
      (node (ref "32U4") (pin "A0") (pinfunction "A0_A0") (pintype "bidirectional"))
      (node (ref "MODE") (pin "SW2") (pinfunction "PIN-2_SW2") (pintype "bidirectional"))
      (node (ref "S11") (pin "3") (pinfunction "2_3") (pintype "passive"))
    )
    (net (code "32") (name "Net-(R2-Pad2)") (class "Default")
      (node (ref "R2") (pin "2") (pinfunction "2_2") (pintype "passive"))
      (node (ref "SK0") (pin "DIN") (pinfunction "DIN_DIN") (pintype "bidirectional"))
    )
    (net (code "33") (name "Net-(RESET-P)") (class "Default")
      (node (ref "32U4") (pin "RST") (pinfunction "RST_RST") (pintype "bidirectional"))
      (node (ref "RESET") (pin "3") (pinfunction "P_3") (pintype "passive"))
      (node (ref "RESET") (pin "4") (pinfunction "P1_4") (pintype "passive"))
    )
    (net (code "34") (name "Net-(SK0-PadDOUT)") (class "Default")
      (node (ref "SK0") (pin "DOUT") (pinfunction "DOUT_DOUT") (pintype "bidirectional"))
      (node (ref "SK1") (pin "DIN") (pinfunction "DIN_DIN") (pintype "bidirectional"))
    )
    (net (code "35") (name "Net-(SK1-PadDOUT)") (class "Default")
      (node (ref "SK1") (pin "DOUT") (pinfunction "DOUT_DOUT") (pintype "bidirectional"))
      (node (ref "SK2") (pin "DIN") (pinfunction "DIN_DIN") (pintype "bidirectional"))
    )
    (net (code "36") (name "Net-(SK2-PadDOUT)") (class "Default")
      (node (ref "SK2") (pin "DOUT") (pinfunction "DOUT_DOUT") (pintype "bidirectional"))
      (node (ref "SK3") (pin "DIN") (pinfunction "DIN_DIN") (pintype "bidirectional"))
    )
    (net (code "37") (name "Net-(SK3-PadDOUT)") (class "Default")
      (node (ref "SK3") (pin "DOUT") (pinfunction "DOUT_DOUT") (pintype "bidirectional"))
      (node (ref "SK4") (pin "DIN") (pinfunction "DIN_DIN") (pintype "bidirectional"))
    )
    (net (code "38") (name "Net-(SK4-PadDOUT)") (class "Default")
      (node (ref "SK4") (pin "DOUT") (pinfunction "DOUT_DOUT") (pintype "bidirectional"))
      (node (ref "SK5") (pin "DIN") (pinfunction "DIN_DIN") (pintype "bidirectional"))
    )
    (net (code "39") (name "Net-(SK5-PadDOUT)") (class "Default")
      (node (ref "SK5") (pin "DOUT") (pinfunction "DOUT_DOUT") (pintype "bidirectional"))
      (node (ref "SK6") (pin "DIN") (pinfunction "DIN_DIN") (pintype "bidirectional"))
    )
    (net (code "40") (name "Net-(SK6-PadDOUT)") (class "Default")
      (node (ref "SK6") (pin "DOUT") (pinfunction "DOUT_DOUT") (pintype "bidirectional"))
      (node (ref "SK7") (pin "DIN") (pinfunction "DIN_DIN") (pintype "bidirectional"))
    )
    (net (code "41") (name "Net-(SK7-PadDOUT)") (class "Default")
      (node (ref "SK7") (pin "DOUT") (pinfunction "DOUT_DOUT") (pintype "bidirectional"))
      (node (ref "SK8") (pin "DIN") (pinfunction "DIN_DIN") (pintype "bidirectional"))
    )
    (net (code "42") (name "Net-(SK8-PadDOUT)") (class "Default")
      (node (ref "SK8") (pin "DOUT") (pinfunction "DOUT_DOUT") (pintype "bidirectional"))
      (node (ref "SK9") (pin "DIN") (pinfunction "DIN_DIN") (pintype "bidirectional"))
    )
    (net (code "43") (name "Net-(SK10-PadDIN)") (class "Default")
      (node (ref "SK10") (pin "DIN") (pinfunction "DIN_DIN") (pintype "bidirectional"))
      (node (ref "SK9") (pin "DOUT") (pinfunction "DOUT_DOUT") (pintype "bidirectional"))
    )
    (net (code "44") (name "Net-(SK10-PadDOUT)") (class "Default")
      (node (ref "SK10") (pin "DOUT") (pinfunction "DOUT_DOUT") (pintype "bidirectional"))
      (node (ref "SK11") (pin "DIN") (pinfunction "DIN_DIN") (pintype "bidirectional"))
    )
    (net (code "45") (name "Net-(SK11-PadDOUT)") (class "Default")
      (node (ref "SK11") (pin "DOUT") (pinfunction "DOUT_DOUT") (pintype "bidirectional"))
      (node (ref "SK12") (pin "DIN") (pinfunction "DIN_DIN") (pintype "bidirectional"))
    )
    (net (code "46") (name "RE1A") (class "Default")
      (node (ref "ENCODER_A") (pin "B") (pinfunction "B_B") (pintype "bidirectional"))
      (node (ref "SJ20") (pin "2") (pinfunction "2_2") (pintype "passive"))
    )
    (net (code "47") (name "RE1B") (class "Default")
      (node (ref "ENCODER_A") (pin "A") (pinfunction "A_A") (pintype "bidirectional"))
      (node (ref "SJ21") (pin "2") (pinfunction "2_2") (pintype "passive"))
    )
    (net (code "48") (name "RE2A") (class "Default")
      (node (ref "ENCODER_B") (pin "B") (pinfunction "B_B") (pintype "bidirectional"))
      (node (ref "SJ18") (pin "2") (pinfunction "2_2") (pintype "passive"))
    )
    (net (code "49") (name "RE2B") (class "Default")
      (node (ref "ENCODER_B") (pin "A") (pinfunction "A_A") (pintype "bidirectional"))
      (node (ref "SJ19") (pin "2") (pinfunction "2_2") (pintype "passive"))
    )
    (net (code "50") (name "ROW_1") (class "Default")
      (node (ref "32U4") (pin "D4") (pinfunction "D4_D4") (pintype "bidirectional"))
      (node (ref "ENCODER_A") (pin "SW-") (pinfunction "SW-_SW-") (pintype "bidirectional"))
      (node (ref "ENCODER_B") (pin "SW-") (pinfunction "SW-_SW-") (pintype "bidirectional"))
      (node (ref "J1") (pin "GND") (pinfunction "GND_GND") (pintype "bidirectional"))
      (node (ref "J2") (pin "7") (pinfunction "7_7") (pintype "passive"))
      (node (ref "KEY1") (pin "SW1") (pinfunction "PIN-1_SW1") (pintype "bidirectional"))
      (node (ref "KEY2") (pin "SW1") (pinfunction "PIN-1_SW1") (pintype "bidirectional"))
      (node (ref "KEY3") (pin "SW1") (pinfunction "PIN-1_SW1") (pintype "bidirectional"))
      (node (ref "KEY4") (pin "SW1") (pinfunction "PIN-1_SW1") (pintype "bidirectional"))
      (node (ref "S3") (pin "3") (pinfunction "2_3") (pintype "passive"))
      (node (ref "S4") (pin "3") (pinfunction "2_3") (pintype "passive"))
    )
    (net (code "51") (name "ROW_2") (class "Default")
      (node (ref "32U4") (pin "D5") (pinfunction "D5_D5") (pintype "bidirectional"))
      (node (ref "J2") (pin "8") (pinfunction "8_8") (pintype "passive"))
      (node (ref "KEY5") (pin "SW1") (pinfunction "PIN-1_SW1") (pintype "bidirectional"))
      (node (ref "KEY6") (pin "SW1") (pinfunction "PIN-1_SW1") (pintype "bidirectional"))
      (node (ref "KEY7") (pin "SW1") (pinfunction "PIN-1_SW1") (pintype "bidirectional"))
      (node (ref "KEY8") (pin "SW1") (pinfunction "PIN-1_SW1") (pintype "bidirectional"))
      (node (ref "S1") (pin "3") (pinfunction "2_3") (pintype "passive"))
      (node (ref "S10") (pin "3") (pinfunction "2_3") (pintype "passive"))
      (node (ref "S2") (pin "3") (pinfunction "2_3") (pintype "passive"))
      (node (ref "S9") (pin "3") (pinfunction "2_3") (pintype "passive"))
    )
    (net (code "52") (name "ROW_3") (class "Default")
      (node (ref "32U4") (pin "A3") (pinfunction "A3_A3") (pintype "bidirectional"))
      (node (ref "KEY10") (pin "SW1") (pinfunction "PIN-1_SW1") (pintype "bidirectional"))
      (node (ref "KEY11") (pin "SW1") (pinfunction "PIN-1_SW1") (pintype "bidirectional"))
      (node (ref "KEY12") (pin "SW1") (pinfunction "PIN-1_SW1") (pintype "bidirectional"))
      (node (ref "KEY9") (pin "SW1") (pinfunction "PIN-1_SW1") (pintype "bidirectional"))
      (node (ref "S5") (pin "3") (pinfunction "2_3") (pintype "passive"))
      (node (ref "S6") (pin "3") (pinfunction "2_3") (pintype "passive"))
      (node (ref "S7") (pin "3") (pinfunction "2_3") (pintype "passive"))
      (node (ref "S8") (pin "3") (pinfunction "2_3") (pintype "passive"))
    )
    (net (code "53") (name "SCL") (class "Default")
      (node (ref "32U4") (pin "D3") (pinfunction "D3_D3") (pintype "bidirectional"))
      (node (ref "J2") (pin "6") (pinfunction "6_6") (pintype "passive"))
      (node (ref "J3") (pin "4") (pinfunction "4_4") (pintype "passive"))
    )
    (net (code "54") (name "SDA") (class "Default")
      (node (ref "32U4") (pin "D2") (pinfunction "D2_D2") (pintype "bidirectional"))
      (node (ref "J2") (pin "5") (pinfunction "5_5") (pintype "passive"))
      (node (ref "J3") (pin "3") (pinfunction "3_3") (pintype "passive"))
    )
    (net (code "55") (name "unconnected-(J1-PadRSH)") (class "Default")
      (node (ref "J1") (pin "RSH") (pinfunction "RSH_RSH") (pintype "bidirectional"))
    )
    (net (code "56") (name "unconnected-(J1-PadTSH)") (class "Default")
      (node (ref "J1") (pin "TSH") (pinfunction "TSH_TSH") (pintype "bidirectional"))
    )
    (net (code "57") (name "unconnected-(SK12-PadDOUT)") (class "Default")
      (node (ref "SK12") (pin "DOUT") (pinfunction "DOUT_DOUT") (pintype "bidirectional"))
    )
  )
)
